# Encoder.net
KiCad netlist of a schematic drawn in Altium Designer
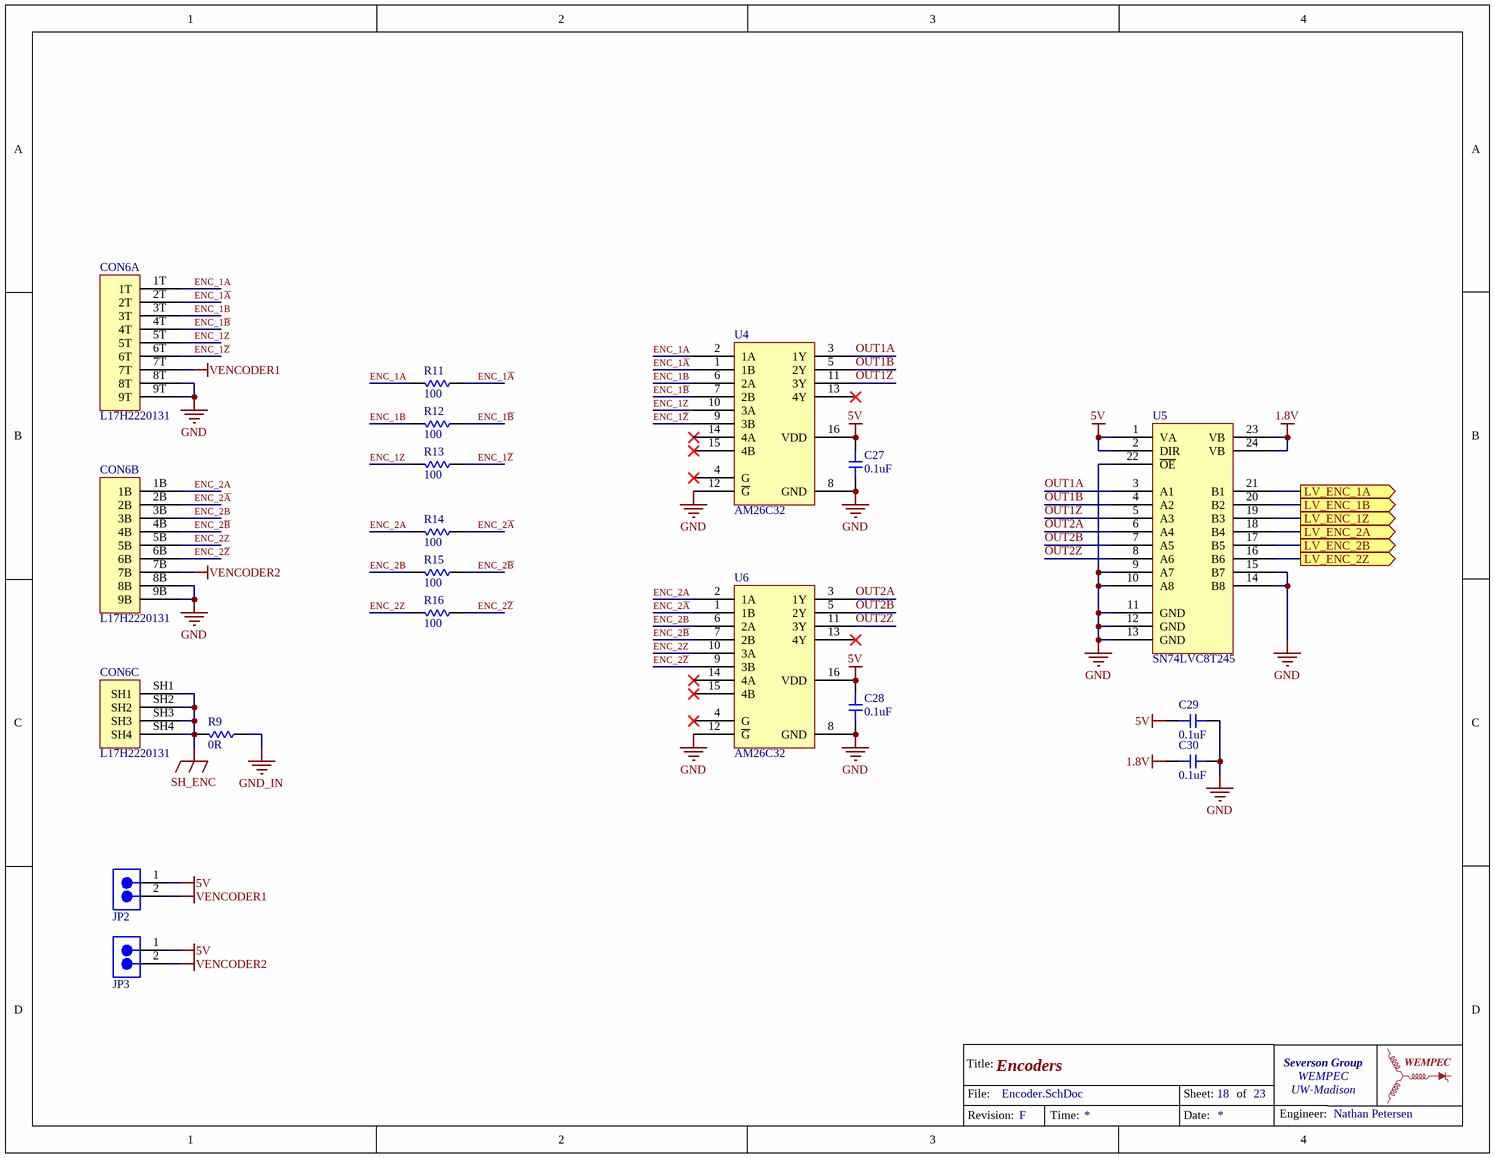
[diagram p0: Encoder.SchDoc]

(export (version "E")
  (design (tool "Eeschema 10.0.6"))
  (components
    (comp (ref "C27")
      (value "0.1uF")
      (footprint "0603-CAP")
      (description "Capacitor")
      (libsource (lib "AMDC") (part "Capacitor"))
    )
    (comp (ref "C28")
      (value "0.1uF")
      (footprint "0603-CAP")
      (description "Capacitor")
      (libsource (lib "AMDC") (part "Capacitor"))
    )
    (comp (ref "C29")
      (value "0.1uF")
      (footprint "0603-CAP")
      (description "Capacitor")
      (libsource (lib "AMDC") (part "Capacitor"))
    )
    (comp (ref "C30")
      (value "0.1uF")
      (footprint "0603-CAP")
      (description "Capacitor")
      (libsource (lib "AMDC") (part "Capacitor"))
    )
    (comp (ref "CON6")
      (value "L17H2220131")
      (footprint "L17H2220131")
      (description "CONN D-SUB RCPT 9POS R/A SLDR")
      (libsource (lib "AMDC") (part "L17H2220131"))
    )
    (comp (ref "JP2")
      (value "Jumper2")
      (footprint "PIN_HEADER_1x2")
      (libsource (lib "AMDC") (part "Jumper2"))
    )
    (comp (ref "JP3")
      (value "Jumper2")
      (footprint "PIN_HEADER_1x2")
      (libsource (lib "AMDC") (part "Jumper2"))
    )
    (comp (ref "R9")
      (value "0R")
      (footprint "1206-RES")
      (description "Resistor")
      (libsource (lib "AMDC") (part "Resistor"))
    )
    (comp (ref "R11")
      (value "100")
      (footprint "0603-RES")
      (description "Resistor")
      (libsource (lib "AMDC") (part "Resistor"))
    )
    (comp (ref "R12")
      (value "100")
      (footprint "0603-RES")
      (description "Resistor")
      (libsource (lib "AMDC") (part "Resistor"))
    )
    (comp (ref "R13")
      (value "100")
      (footprint "0603-RES")
      (description "Resistor")
      (libsource (lib "AMDC") (part "Resistor"))
    )
    (comp (ref "R14")
      (value "100")
      (footprint "0603-RES")
      (description "Resistor")
      (libsource (lib "AMDC") (part "Resistor"))
    )
    (comp (ref "R15")
      (value "100")
      (footprint "0603-RES")
      (description "Resistor")
      (libsource (lib "AMDC") (part "Resistor"))
    )
    (comp (ref "R16")
      (value "100")
      (footprint "0603-RES")
      (description "Resistor")
      (libsource (lib "AMDC") (part "Resistor"))
    )
    (comp (ref "U4")
      (value "AM26C32")
      (footprint "TSOP65P640X120-16N")
      (description "IC RCVR RS422 QUAD DIFF 16TSSOP")
      (libsource (lib "AMDC") (part "AM26C32"))
    )
    (comp (ref "U5")
      (value "SN74LVC8T245")
      (footprint "TSOP65P640X120-24N")
      (description "IC BUS TRANSCVR 8BIT 24TSSOP")
      (libsource (lib "AMDC") (part "SN74LVC8T245PWR"))
    )
    (comp (ref "U6")
      (value "AM26C32")
      (footprint "TSOP65P640X120-16N")
      (description "IC RCVR RS422 QUAD DIFF 16TSSOP")
      (libsource (lib "AMDC") (part "AM26C32"))
    )
  )
  (nets
    (net (code "1") (name "/ENC_1A") (class "Default")
      (node (ref "CON6") (pin "1T") (pinfunction "1T_1T") (pintype "passive"))
      (node (ref "R11") (pin "2") (pinfunction "2_2") (pintype "passive"))
      (node (ref "U4") (pin "2") (pinfunction "1A_2") (pintype "passive"))
    )
    (net (code "2") (name "/ENC_1B") (class "Default")
      (node (ref "CON6") (pin "3T") (pinfunction "3T_3T") (pintype "passive"))
      (node (ref "R12") (pin "2") (pinfunction "2_2") (pintype "passive"))
      (node (ref "U4") (pin "6") (pinfunction "2A_6") (pintype "passive"))
    )
    (net (code "3") (name "/ENC_1Z") (class "Default")
      (node (ref "CON6") (pin "5T") (pinfunction "5T_5T") (pintype "passive"))
      (node (ref "R13") (pin "2") (pinfunction "2_2") (pintype "passive"))
      (node (ref "U4") (pin "10") (pinfunction "3A_10") (pintype "passive"))
    )
    (net (code "4") (name "/ENC_1~{A}") (class "Default")
      (node (ref "CON6") (pin "2T") (pinfunction "2T_2T") (pintype "passive"))
      (node (ref "R11") (pin "1") (pinfunction "1_1") (pintype "passive"))
      (node (ref "U4") (pin "1") (pinfunction "1B_1") (pintype "passive"))
    )
    (net (code "5") (name "/ENC_1~{B}") (class "Default")
      (node (ref "CON6") (pin "4T") (pinfunction "4T_4T") (pintype "passive"))
      (node (ref "R12") (pin "1") (pinfunction "1_1") (pintype "passive"))
      (node (ref "U4") (pin "7") (pinfunction "2B_7") (pintype "passive"))
    )
    (net (code "6") (name "/ENC_1~{Z}") (class "Default")
      (node (ref "CON6") (pin "6T") (pinfunction "6T_6T") (pintype "passive"))
      (node (ref "R13") (pin "1") (pinfunction "1_1") (pintype "passive"))
      (node (ref "U4") (pin "9") (pinfunction "3B_9") (pintype "passive"))
    )
    (net (code "7") (name "/ENC_2A") (class "Default")
      (node (ref "CON6") (pin "1B") (pinfunction "1B_1B") (pintype "passive"))
      (node (ref "R14") (pin "2") (pinfunction "2_2") (pintype "passive"))
      (node (ref "U6") (pin "2") (pinfunction "1A_2") (pintype "passive"))
    )
    (net (code "8") (name "/ENC_2B") (class "Default")
      (node (ref "CON6") (pin "3B") (pinfunction "3B_3B") (pintype "passive"))
      (node (ref "R15") (pin "2") (pinfunction "2_2") (pintype "passive"))
      (node (ref "U6") (pin "6") (pinfunction "2A_6") (pintype "passive"))
    )
    (net (code "9") (name "/ENC_2Z") (class "Default")
      (node (ref "CON6") (pin "5B") (pinfunction "5B_5B") (pintype "passive"))
      (node (ref "R16") (pin "2") (pinfunction "2_2") (pintype "passive"))
      (node (ref "U6") (pin "10") (pinfunction "3A_10") (pintype "passive"))
    )
    (net (code "10") (name "/ENC_2~{A}") (class "Default")
      (node (ref "CON6") (pin "2B") (pinfunction "2B_2B") (pintype "passive"))
      (node (ref "R14") (pin "1") (pinfunction "1_1") (pintype "passive"))
      (node (ref "U6") (pin "1") (pinfunction "1B_1") (pintype "passive"))
    )
    (net (code "11") (name "/ENC_2~{B}") (class "Default")
      (node (ref "CON6") (pin "4B") (pinfunction "4B_4B") (pintype "passive"))
      (node (ref "R15") (pin "1") (pinfunction "1_1") (pintype "passive"))
      (node (ref "U6") (pin "7") (pinfunction "2B_7") (pintype "passive"))
    )
    (net (code "12") (name "/ENC_2~{Z}") (class "Default")
      (node (ref "CON6") (pin "6B") (pinfunction "6B_6B") (pintype "passive"))
      (node (ref "R16") (pin "1") (pinfunction "1_1") (pintype "passive"))
      (node (ref "U6") (pin "9") (pinfunction "3B_9") (pintype "passive"))
    )
    (net (code "13") (name "/LV_ENC_1A") (class "Default")
      (node (ref "U5") (pin "21") (pinfunction "B1_21") (pintype "passive"))
    )
    (net (code "14") (name "/LV_ENC_1B") (class "Default")
      (node (ref "U5") (pin "20") (pinfunction "B2_20") (pintype "passive"))
    )
    (net (code "15") (name "/LV_ENC_1Z") (class "Default")
      (node (ref "U5") (pin "19") (pinfunction "B3_19") (pintype "passive"))
    )
    (net (code "16") (name "/LV_ENC_2A") (class "Default")
      (node (ref "U5") (pin "18") (pinfunction "B4_18") (pintype "passive"))
    )
    (net (code "17") (name "/LV_ENC_2B") (class "Default")
      (node (ref "U5") (pin "17") (pinfunction "B5_17") (pintype "passive"))
    )
    (net (code "18") (name "/LV_ENC_2Z") (class "Default")
      (node (ref "U5") (pin "16") (pinfunction "B6_16") (pintype "passive"))
    )
    (net (code "19") (name "/OUT1A") (class "Default")
      (node (ref "U4") (pin "3") (pinfunction "1Y_3") (pintype "passive"))
      (node (ref "U5") (pin "3") (pinfunction "A1_3") (pintype "passive"))
    )
    (net (code "20") (name "/OUT1B") (class "Default")
      (node (ref "U4") (pin "5") (pinfunction "2Y_5") (pintype "passive"))
      (node (ref "U5") (pin "4") (pinfunction "A2_4") (pintype "passive"))
    )
    (net (code "21") (name "/OUT1Z") (class "Default")
      (node (ref "U4") (pin "11") (pinfunction "3Y_11") (pintype "passive"))
      (node (ref "U5") (pin "5") (pinfunction "A3_5") (pintype "passive"))
    )
    (net (code "22") (name "/OUT2A") (class "Default")
      (node (ref "U5") (pin "6") (pinfunction "A4_6") (pintype "passive"))
      (node (ref "U6") (pin "3") (pinfunction "1Y_3") (pintype "passive"))
    )
    (net (code "23") (name "/OUT2B") (class "Default")
      (node (ref "U5") (pin "7") (pinfunction "A5_7") (pintype "passive"))
      (node (ref "U6") (pin "5") (pinfunction "2Y_5") (pintype "passive"))
    )
    (net (code "24") (name "/OUT2Z") (class "Default")
      (node (ref "U5") (pin "8") (pinfunction "A6_8") (pintype "passive"))
      (node (ref "U6") (pin "11") (pinfunction "3Y_11") (pintype "passive"))
    )
    (net (code "25") (name "1.8V") (class "Default")
      (node (ref "C30") (pin "1") (pinfunction "1_1") (pintype "passive"))
      (node (ref "U5") (pin "23") (pinfunction "VB_23") (pintype "passive"))
      (node (ref "U5") (pin "24") (pinfunction "VB_24") (pintype "passive"))
    )
    (net (code "26") (name "5V") (class "Default")
      (node (ref "C27") (pin "2") (pinfunction "2_2") (pintype "passive"))
      (node (ref "C28") (pin "2") (pinfunction "2_2") (pintype "passive"))
      (node (ref "C29") (pin "1") (pinfunction "1_1") (pintype "passive"))
      (node (ref "JP2") (pin "1") (pinfunction "76_1") (pintype "passive"))
      (node (ref "JP3") (pin "1") (pinfunction "76_1") (pintype "passive"))
      (node (ref "U4") (pin "16") (pinfunction "VDD_16") (pintype "passive"))
      (node (ref "U5") (pin "1") (pinfunction "VA_1") (pintype "passive"))
      (node (ref "U5") (pin "2") (pinfunction "DIR_2") (pintype "passive"))
      (node (ref "U6") (pin "16") (pinfunction "VDD_16") (pintype "passive"))
    )
    (net (code "27") (name "GND") (class "Default")
      (node (ref "C27") (pin "1") (pinfunction "1_1") (pintype "passive"))
      (node (ref "C28") (pin "1") (pinfunction "1_1") (pintype "passive"))
      (node (ref "C29") (pin "2") (pinfunction "2_2") (pintype "passive"))
      (node (ref "C30") (pin "2") (pinfunction "2_2") (pintype "passive"))
      (node (ref "CON6") (pin "8B") (pinfunction "8B_8B") (pintype "passive"))
      (node (ref "CON6") (pin "8T") (pinfunction "8T_8T") (pintype "passive"))
      (node (ref "CON6") (pin "9B") (pinfunction "9B_9B") (pintype "passive"))
      (node (ref "CON6") (pin "9T") (pinfunction "9T_9T") (pintype "passive"))
      (node (ref "U4") (pin "12") (pinfunction "~{G}_12") (pintype "passive"))
      (node (ref "U4") (pin "8") (pinfunction "GND_8") (pintype "passive"))
      (node (ref "U5") (pin "10") (pinfunction "A8_10") (pintype "passive"))
      (node (ref "U5") (pin "11") (pinfunction "GND_11") (pintype "passive"))
      (node (ref "U5") (pin "12") (pinfunction "GND_12") (pintype "passive"))
      (node (ref "U5") (pin "13") (pinfunction "GND_13") (pintype "passive"))
      (node (ref "U5") (pin "14") (pinfunction "B8_14") (pintype "passive"))
      (node (ref "U5") (pin "15") (pinfunction "B7_15") (pintype "passive"))
      (node (ref "U5") (pin "22") (pinfunction "~{OE}_22") (pintype "passive"))
      (node (ref "U5") (pin "9") (pinfunction "A7_9") (pintype "passive"))
      (node (ref "U6") (pin "12") (pinfunction "~{G}_12") (pintype "passive"))
      (node (ref "U6") (pin "8") (pinfunction "GND_8") (pintype "passive"))
    )
    (net (code "28") (name "GND_IN") (class "Default")
      (node (ref "R9") (pin "1") (pinfunction "1_1") (pintype "passive"))
    )
    (net (code "29") (name "SH_ENC") (class "Default")
      (node (ref "CON6") (pin "SH1") (pinfunction "SH1_SH1") (pintype "passive"))
      (node (ref "CON6") (pin "SH2") (pinfunction "SH2_SH2") (pintype "passive"))
      (node (ref "CON6") (pin "SH3") (pinfunction "SH3_SH3") (pintype "passive"))
      (node (ref "CON6") (pin "SH4") (pinfunction "SH4_SH4") (pintype "passive"))
      (node (ref "R9") (pin "2") (pinfunction "2_2") (pintype "passive"))
    )
    (net (code "30") (name "VENCODER1") (class "Default")
      (node (ref "CON6") (pin "7T") (pinfunction "7T_7T") (pintype "passive"))
      (node (ref "JP2") (pin "2") (pinfunction "75_2") (pintype "passive"))
    )
    (net (code "31") (name "VENCODER2") (class "Default")
      (node (ref "CON6") (pin "7B") (pinfunction "7B_7B") (pintype "passive"))
      (node (ref "JP3") (pin "2") (pinfunction "75_2") (pintype "passive"))
    )
    (net (code "32") (name "unconnected-(U4-4A-Pad14)") (class "Default")
      (node (ref "U4") (pin "14") (pinfunction "4A_14") (pintype "passive+no_connect"))
    )
    (net (code "33") (name "unconnected-(U4-4B-Pad15)") (class "Default")
      (node (ref "U4") (pin "15") (pinfunction "4B_15") (pintype "passive+no_connect"))
    )
    (net (code "34") (name "unconnected-(U4-4Y-Pad13)") (class "Default")
      (node (ref "U4") (pin "13") (pinfunction "4Y_13") (pintype "passive+no_connect"))
    )
    (net (code "35") (name "unconnected-(U4-G-Pad4)") (class "Default")
      (node (ref "U4") (pin "4") (pinfunction "G_4") (pintype "passive+no_connect"))
    )
    (net (code "36") (name "unconnected-(U6-4A-Pad14)") (class "Default")
      (node (ref "U6") (pin "14") (pinfunction "4A_14") (pintype "passive+no_connect"))
    )
    (net (code "37") (name "unconnected-(U6-4B-Pad15)") (class "Default")
      (node (ref "U6") (pin "15") (pinfunction "4B_15") (pintype "passive+no_connect"))
    )
    (net (code "38") (name "unconnected-(U6-4Y-Pad13)") (class "Default")
      (node (ref "U6") (pin "13") (pinfunction "4Y_13") (pintype "passive+no_connect"))
    )
    (net (code "39") (name "unconnected-(U6-G-Pad4)") (class "Default")
      (node (ref "U6") (pin "4") (pinfunction "G_4") (pintype "passive+no_connect"))
    )
  )
)
